# CH340C_USB-C_v1_complete.net
KiCad netlist of a schematic drawn in EAGLE
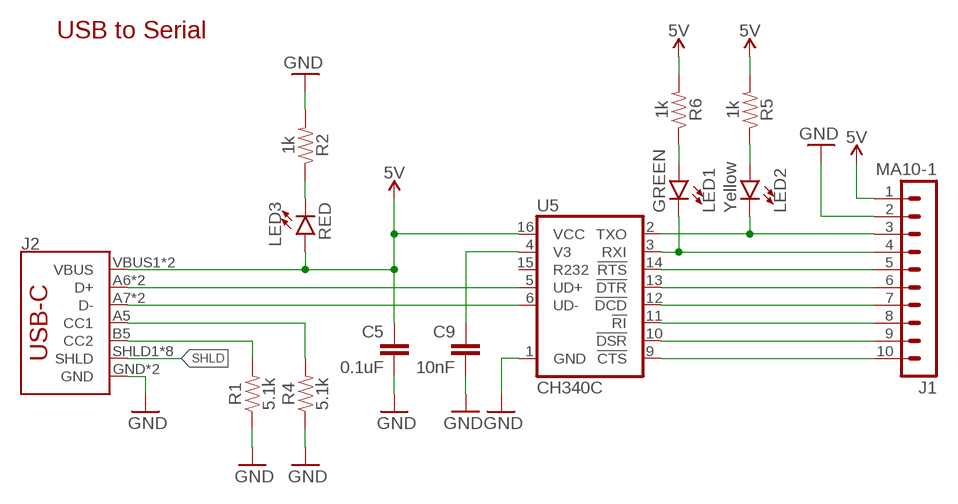
[diagram p0: schematic, sheet 1]

(export (version "E")
  (design (tool "Eeschema 10.0.6"))
  (components
    (comp (ref "C5")
      (value "0.1uF")
      (footprint "eagle-import:0603")
      (libsource (lib "eagle-import") (part "0.1UF-0603-25V-(+80/-20%)"))
    )
    (comp (ref "C9")
      (value "10nF")
      (footprint "eagle-import:0603")
      (libsource (lib "eagle-import") (part "10NF-0603-50V-10%"))
    )
    (comp (ref "J1")
      (value "MA10-1")
      (footprint "eagle-import:MA10-1")
      (libsource (lib "eagle-import") (part "MA10-1"))
    )
    (comp (ref "J2")
      (value "USB_C16PIN")
      (footprint "eagle-import:USB-C-16P")
      (libsource (lib "eagle-import") (part "USB_C16PIN"))
    )
    (comp (ref "LED1")
      (value "GREEN")
      (footprint "eagle-import:LED-0603")
      (libsource (lib "eagle-import") (part "LED-GREEN0603"))
    )
    (comp (ref "LED2")
      (value "Yellow")
      (footprint "eagle-import:LED-0603")
      (libsource (lib "eagle-import") (part "LED-YELLOW0603"))
    )
    (comp (ref "LED3")
      (value "RED")
      (footprint "eagle-import:LED-0603")
      (libsource (lib "eagle-import") (part "LED-GREEN0603"))
    )
    (comp (ref "R1")
      (value "5.1k")
      (footprint "eagle-import:0603")
      (libsource (lib "eagle-import") (part "5.1KOHM5.1KOHM-0603-1/10W-1%"))
    )
    (comp (ref "R2")
      (value "1k")
      (footprint "eagle-import:0603")
      (libsource (lib "eagle-import") (part "1KOHM-0603-1/10W-1%"))
    )
    (comp (ref "R4")
      (value "5.1k")
      (footprint "eagle-import:0603")
      (libsource (lib "eagle-import") (part "5.1KOHM5.1KOHM-0603-1/10W-1%"))
    )
    (comp (ref "R5")
      (value "1k")
      (footprint "eagle-import:0603")
      (libsource (lib "eagle-import") (part "1KOHM-0603-1/10W-1%"))
    )
    (comp (ref "R6")
      (value "1k")
      (footprint "eagle-import:0603")
      (libsource (lib "eagle-import") (part "1KOHM-0603-1/10W-1%"))
    )
    (comp (ref "U5")
      (value "CH340C")
      (footprint "eagle-import:SO016")
      (libsource (lib "eagle-import") (part "CH340C"))
    )
  )
  (nets
    (net (code "1") (name "5V") (class "Default")
      (node (ref "C5") (pin "1") (pinfunction "1_1") (pintype "passive"))
      (node (ref "J1") (pin "1") (pinfunction "1_1") (pintype "passive"))
      (node (ref "J2") (pin "VBUS1") (pinfunction "VBUS_VBUS1") (pintype "bidirectional"))
      (node (ref "J2") (pin "VBUS2") (pinfunction "VBUS_VBUS2") (pintype "bidirectional"))
      (node (ref "LED3") (pin "A") (pinfunction "A_A") (pintype "passive"))
      (node (ref "R5") (pin "2") (pinfunction "2_2") (pintype "passive"))
      (node (ref "R6") (pin "2") (pinfunction "2_2") (pintype "passive"))
      (node (ref "U5") (pin "16") (pinfunction "VCC_16") (pintype "bidirectional"))
    )
    (net (code "2") (name "GND") (class "Default")
      (node (ref "C5") (pin "2") (pinfunction "2_2") (pintype "passive"))
      (node (ref "C9") (pin "2") (pinfunction "2_2") (pintype "passive"))
      (node (ref "J1") (pin "2") (pinfunction "2_2") (pintype "passive"))
      (node (ref "J2") (pin "GND") (pinfunction "GND_GND") (pintype "bidirectional"))
      (node (ref "J2") (pin "GND2") (pinfunction "GND_GND2") (pintype "bidirectional"))
      (node (ref "R1") (pin "1") (pinfunction "1_1") (pintype "passive"))
      (node (ref "R2") (pin "2") (pinfunction "2_2") (pintype "passive"))
      (node (ref "R4") (pin "1") (pinfunction "1_1") (pintype "passive"))
      (node (ref "U5") (pin "1") (pinfunction "GND_1") (pintype "bidirectional"))
    )
    (net (code "3") (name "Net-(J2-CC1)") (class "Default")
      (node (ref "J2") (pin "A5") (pinfunction "CC1_A5") (pintype "bidirectional"))
      (node (ref "R4") (pin "2") (pinfunction "2_2") (pintype "passive"))
    )
    (net (code "4") (name "Net-(J2-CC2)") (class "Default")
      (node (ref "J2") (pin "B5") (pinfunction "CC2_B5") (pintype "bidirectional"))
      (node (ref "R1") (pin "2") (pinfunction "2_2") (pintype "passive"))
    )
    (net (code "5") (name "Net-(LED1-PadA)") (class "Default")
      (node (ref "LED1") (pin "A") (pinfunction "A_A") (pintype "passive"))
      (node (ref "R6") (pin "1") (pinfunction "1_1") (pintype "passive"))
    )
    (net (code "6") (name "Net-(LED2-PadA)") (class "Default")
      (node (ref "LED2") (pin "A") (pinfunction "A_A") (pintype "passive"))
      (node (ref "R5") (pin "1") (pinfunction "1_1") (pintype "passive"))
    )
    (net (code "7") (name "Net-(LED3-PadC)") (class "Default")
      (node (ref "LED3") (pin "C") (pinfunction "C_C") (pintype "passive"))
      (node (ref "R2") (pin "1") (pinfunction "1_1") (pintype "passive"))
    )
    (net (code "8") (name "Net-(U5-RXI)") (class "Default")
      (node (ref "J1") (pin "4") (pinfunction "4_4") (pintype "passive"))
      (node (ref "LED1") (pin "C") (pinfunction "C_C") (pintype "passive"))
      (node (ref "U5") (pin "3") (pinfunction "RXI_3") (pintype "bidirectional"))
    )
    (net (code "9") (name "Net-(U5-TXO)") (class "Default")
      (node (ref "J1") (pin "3") (pinfunction "3_3") (pintype "passive"))
      (node (ref "LED2") (pin "C") (pinfunction "C_C") (pintype "passive"))
      (node (ref "U5") (pin "2") (pinfunction "TXO_2") (pintype "bidirectional"))
    )
    (net (code "10") (name "Net-(U5-UD+)") (class "Default")
      (node (ref "J2") (pin "A6") (pinfunction "D+_A6") (pintype "bidirectional"))
      (node (ref "J2") (pin "B6") (pinfunction "D+_B6") (pintype "bidirectional"))
      (node (ref "U5") (pin "5") (pinfunction "UD+_5") (pintype "bidirectional"))
    )
    (net (code "11") (name "Net-(U5-UD-)") (class "Default")
      (node (ref "J2") (pin "A7") (pinfunction "D-_A7") (pintype "bidirectional"))
      (node (ref "J2") (pin "B7") (pinfunction "D-_B7") (pintype "bidirectional"))
      (node (ref "U5") (pin "6") (pinfunction "UD-_6") (pintype "bidirectional"))
    )
    (net (code "12") (name "Net-(U5-V3)") (class "Default")
      (node (ref "C9") (pin "1") (pinfunction "1_1") (pintype "passive"))
      (node (ref "U5") (pin "4") (pinfunction "V3_4") (pintype "bidirectional"))
    )
    (net (code "13") (name "Net-(U5-~{CTS})") (class "Default")
      (node (ref "J1") (pin "10") (pinfunction "10_10") (pintype "passive"))
      (node (ref "U5") (pin "9") (pinfunction "~{CTS}_9") (pintype "bidirectional"))
    )
    (net (code "14") (name "Net-(U5-~{DCD})") (class "Default")
      (node (ref "J1") (pin "7") (pinfunction "7_7") (pintype "passive"))
      (node (ref "U5") (pin "12") (pinfunction "~{DCD}_12") (pintype "bidirectional"))
    )
    (net (code "15") (name "Net-(U5-~{DSR})") (class "Default")
      (node (ref "J1") (pin "9") (pinfunction "9_9") (pintype "passive"))
      (node (ref "U5") (pin "10") (pinfunction "~{DSR}_10") (pintype "bidirectional"))
    )
    (net (code "16") (name "Net-(U5-~{DTR})") (class "Default")
      (node (ref "J1") (pin "6") (pinfunction "6_6") (pintype "passive"))
      (node (ref "U5") (pin "13") (pinfunction "~{DTR}_13") (pintype "bidirectional"))
    )
    (net (code "17") (name "Net-(U5-~{RI})") (class "Default")
      (node (ref "J1") (pin "8") (pinfunction "8_8") (pintype "passive"))
      (node (ref "U5") (pin "11") (pinfunction "~{RI}_11") (pintype "bidirectional"))
    )
    (net (code "18") (name "Net-(U5-~{RTS})") (class "Default")
      (node (ref "J1") (pin "5") (pinfunction "5_5") (pintype "passive"))
      (node (ref "U5") (pin "14") (pinfunction "~{RTS}_14") (pintype "bidirectional"))
    )
    (net (code "19") (name "SHLD") (class "Default")
      (node (ref "J2") (pin "SHLD1") (pinfunction "SHLD_SHLD1") (pintype "bidirectional"))
      (node (ref "J2") (pin "SHLD2") (pinfunction "SHLD_SHLD2") (pintype "bidirectional"))
      (node (ref "J2") (pin "SHLD3") (pinfunction "SHLD_SHLD3") (pintype "bidirectional"))
      (node (ref "J2") (pin "SHLD4") (pinfunction "SHLD_SHLD4") (pintype "bidirectional"))
      (node (ref "J2") (pin "SHLD5") (pinfunction "SHLD_SHLD5") (pintype "bidirectional"))
      (node (ref "J2") (pin "SHLD6") (pinfunction "SHLD_SHLD6") (pintype "bidirectional"))
      (node (ref "J2") (pin "SHLD7") (pinfunction "SHLD_SHLD7") (pintype "bidirectional"))
      (node (ref "J2") (pin "SHLD8") (pinfunction "SHLD_SHLD8") (pintype "bidirectional"))
    )
    (net (code "20") (name "unconnected-(U5-R232-Pad15)") (class "Default")
      (node (ref "U5") (pin "15") (pinfunction "R232_15") (pintype "bidirectional"))
    )
  )
)
